# 300A_Hall_Power_Meter.net
KiCad netlist of a schematic drawn in EasyEDA Pro
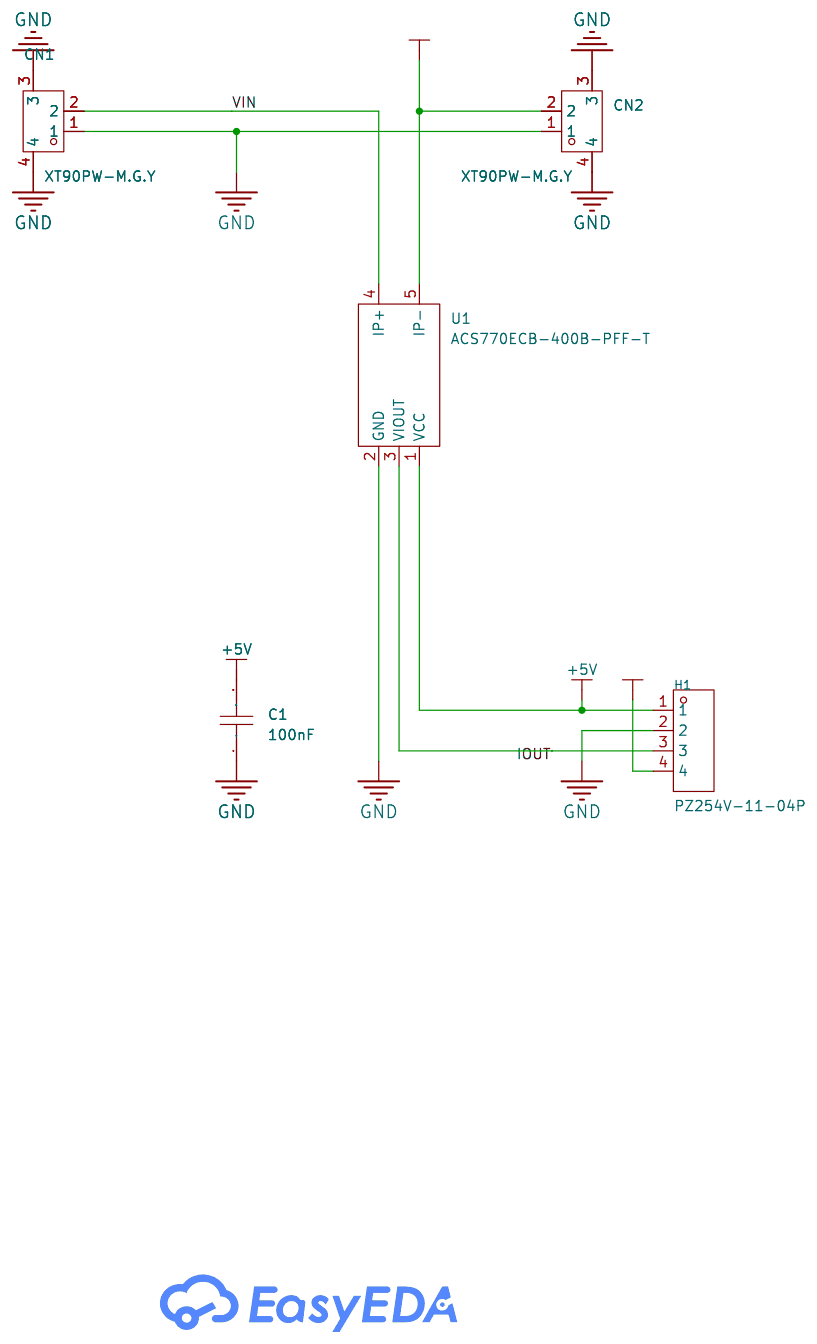
[diagram p0: Current Meter]
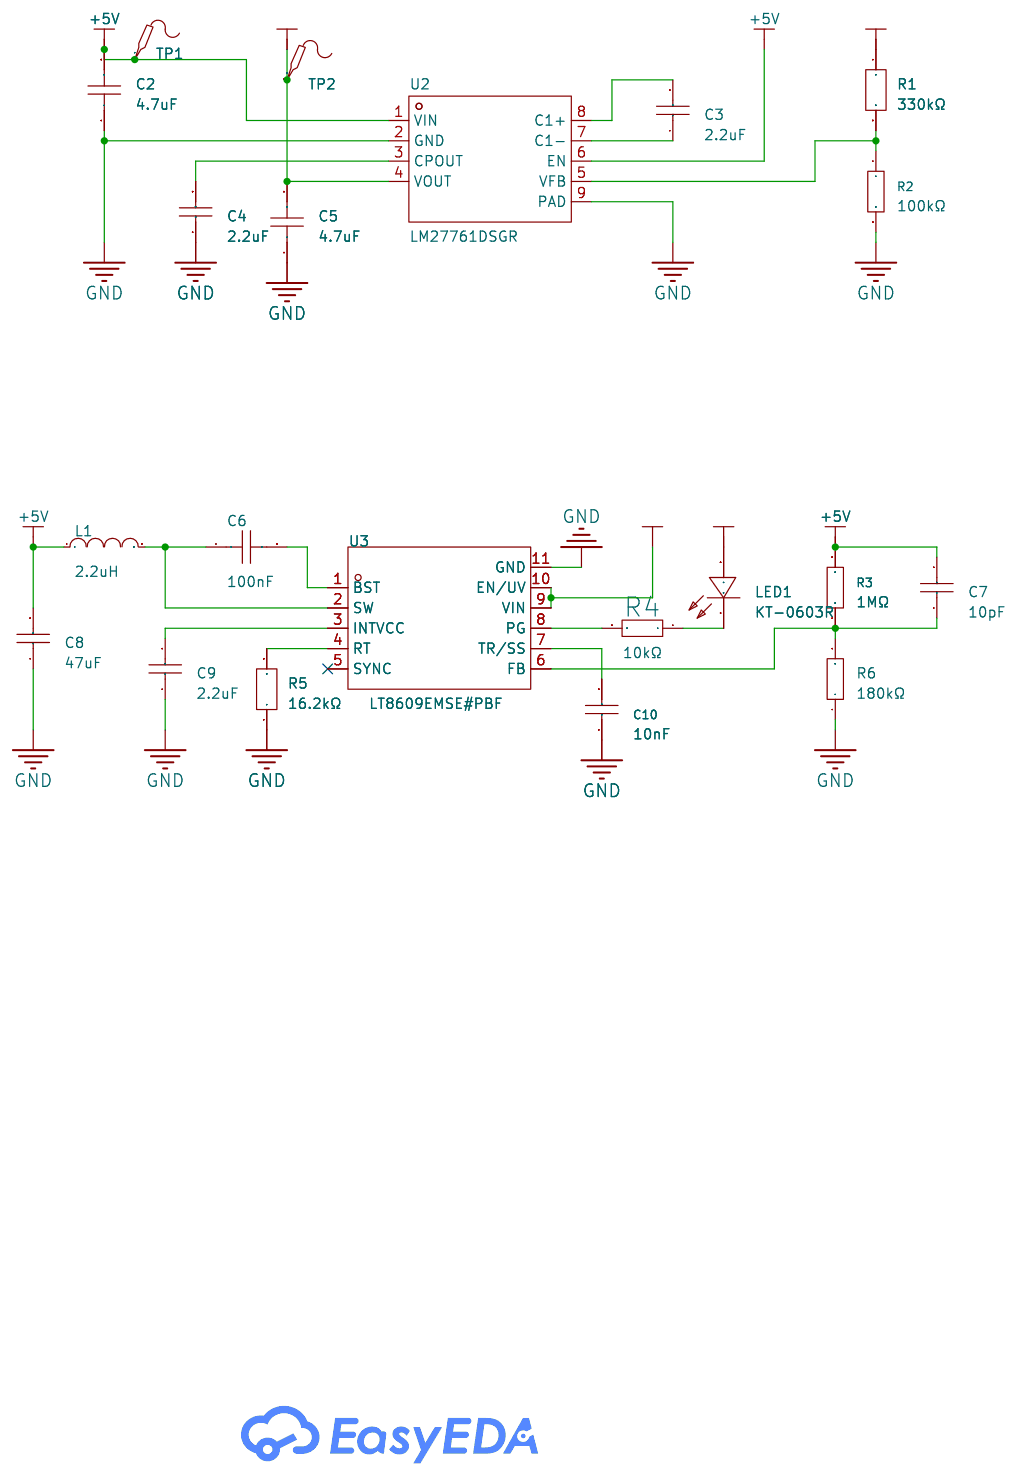
[diagram p1: Buck Converter]
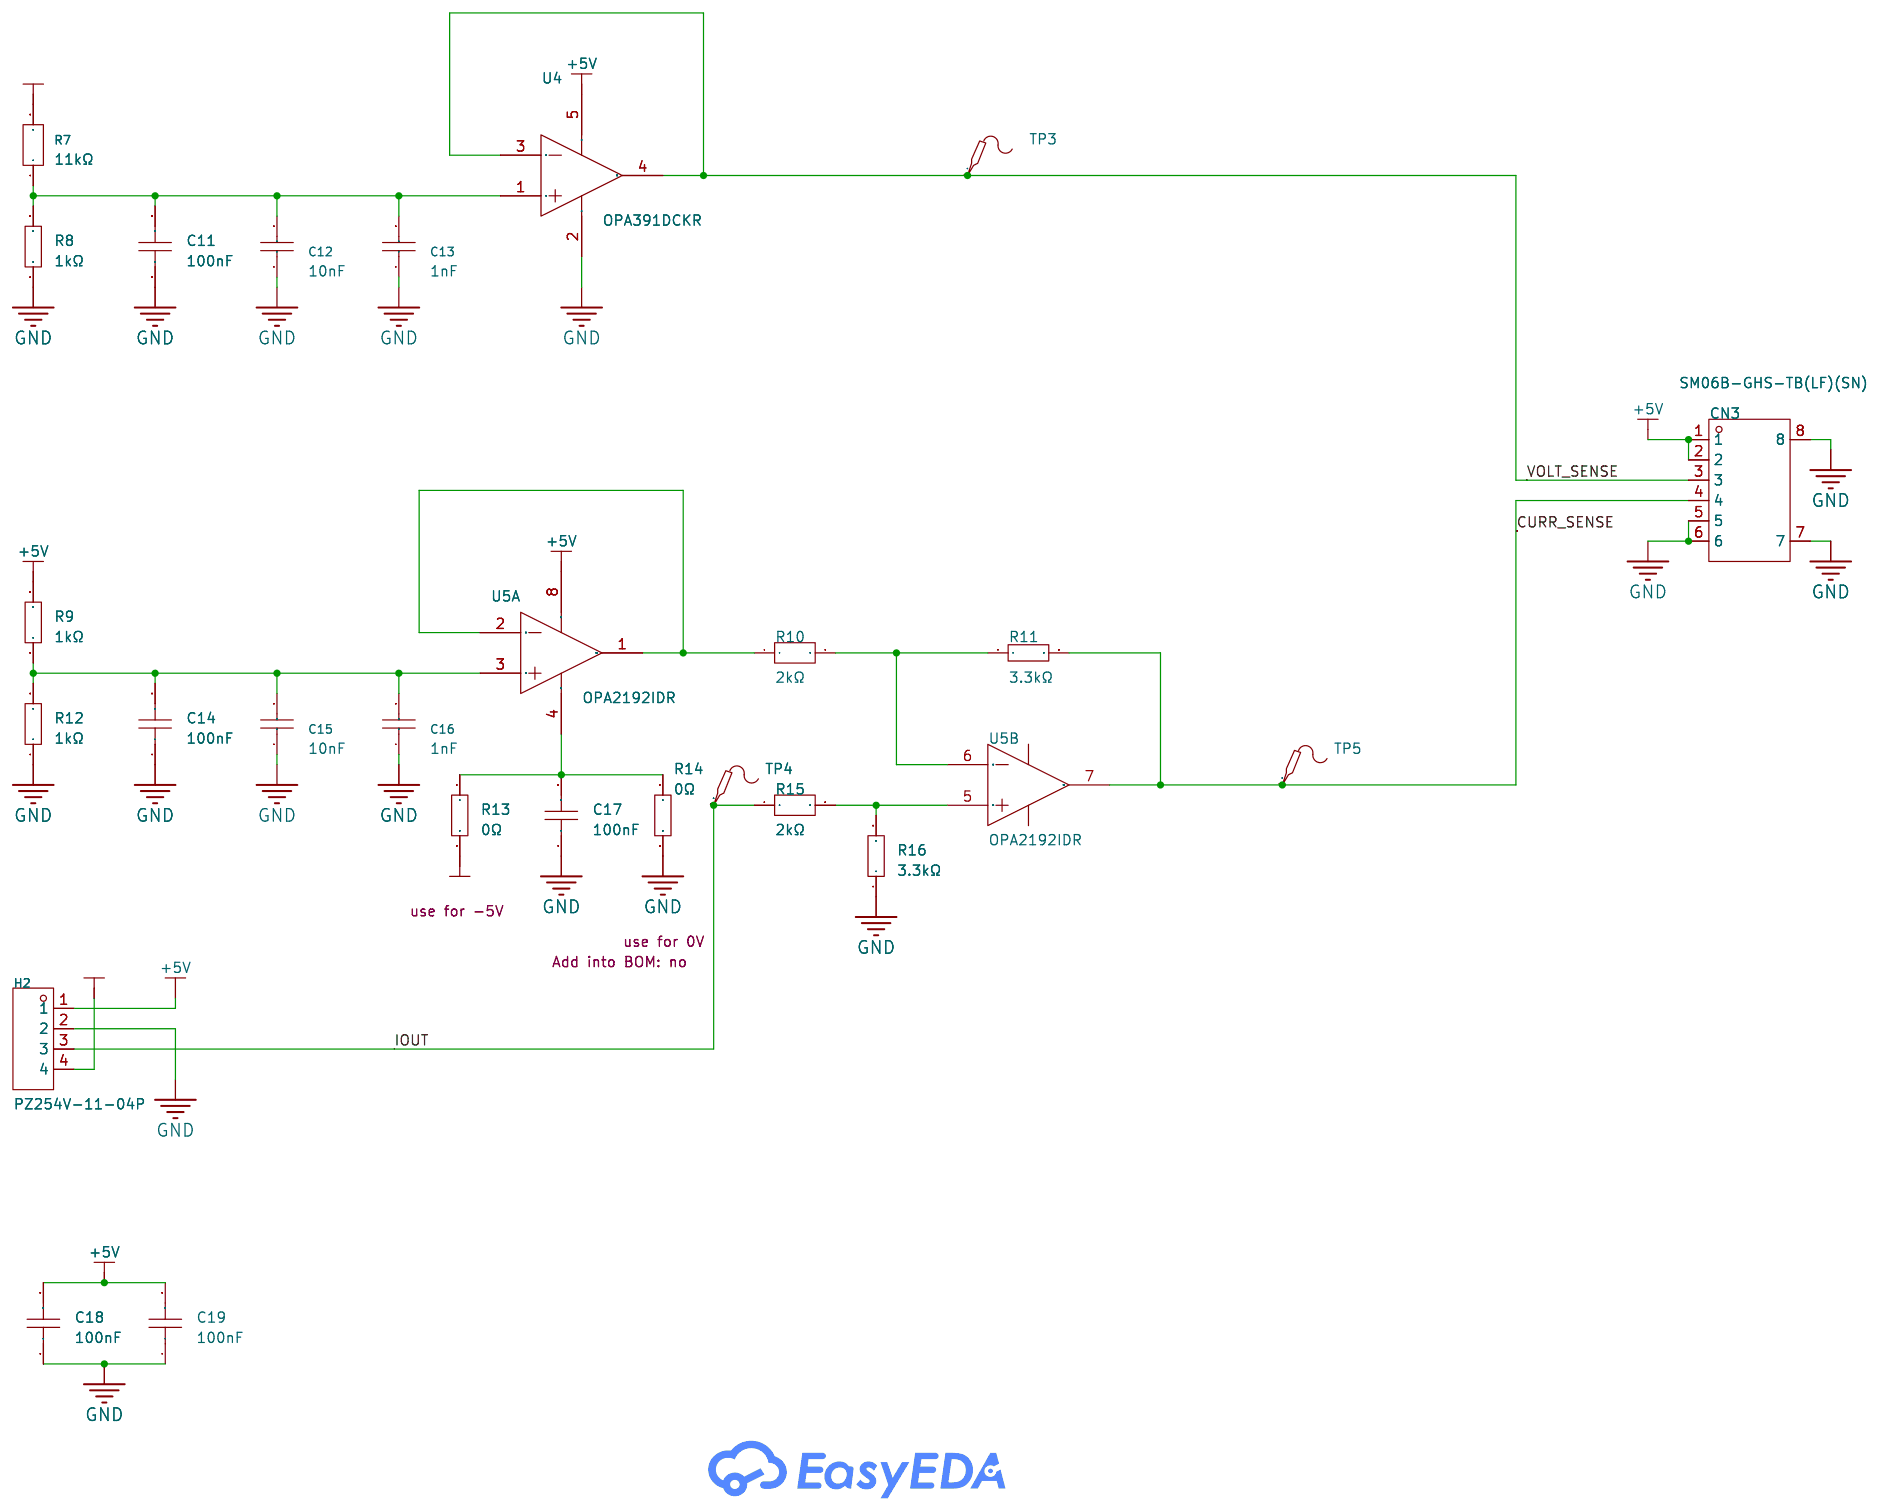
[diagram p2: Signal Processing]

(export (version "E")
  (design (tool "Eeschema 10.0.6"))
  (components
    (comp (ref "C1")
      (value "100nF")
      (footprint "easyedapro:C0402")
      (description "Capacitance:100nF Tolerance:±10% Tolerance:±10% Voltage Rating:16V Temperature Coefficient:X7R")
      (fields
        (field (name "Manufacturer Part") "CL05B104KO5NNNC")
        (field (name "Manufacturer") "SAMSUNG(三星)")
      )
      (libsource (lib "easyedapro") (part "CL05B104KO5NNNC"))
    )
    (comp (ref "CN1")
      (value "XT90PW-M.G.Y")
      (footprint "easyedapro:CONN-TH_XT90PW-M.G.Y")
      (fields (field (name "Manufacturer") "AMASS(艾迈斯)"))
      (libsource (lib "easyedapro") (part "XT90PW-M.G.Y"))
    )
    (comp (ref "CN2")
      (value "XT90PW-M.G.Y")
      (footprint "easyedapro:CONN-TH_XT90PW-M.G.Y")
      (fields (field (name "Manufacturer") "AMASS(艾迈斯)"))
      (libsource (lib "easyedapro") (part "XT90PW-M.G.Y"))
    )
    (comp (ref "H1")
      (value "PZ254V-11-04P")
      (footprint "easyedapro:HDR-TH_4P-P2.54-V-M")
      (fields (field (name "Manufacturer") "XFCN(兴飞)"))
      (libsource (lib "easyedapro") (part "PZ254V-11-04P_C2691448"))
    )
    (comp (ref "U1")
      (value "ACS770ECB-400B-PFF-T")
      (footprint "easyedapro:CB-5_L13.0-W10.0-P1.91-LS21.4-BR")
      (fields (field (name "Manufacturer") "ALLEGRO(美国埃戈罗)"))
      (libsource (lib "easyedapro") (part "ACS770ECB-400B-PFF-T"))
    )
    (comp (ref "C2")
      (value "4.7uF")
      (footprint "easyedapro:C0603")
      (description "Capacitance:4.7uF Tolerance:±10% Tolerance:±10% Voltage Rating:16V Temperature Coefficient:X5R")
      (fields
        (field (name "Manufacturer Part") "CL10A475KO8NNNC")
        (field (name "Manufacturer") "SAMSUNG(三星)")
      )
      (libsource (lib "easyedapro") (part "CL10A475KO8NNNC"))
    )
    (comp (ref "C3")
      (value "2.2uF")
      (footprint "easyedapro:C0603")
      (description "Capacitance:2.2uF Tolerance:±10% Tolerance:±10% Voltage Rating:16V Temperature Coefficient:X5R")
      (fields
        (field (name "Manufacturer Part") "CL10A225KO8NNNC")
        (field (name "Manufacturer") "SAMSUNG(三星)")
      )
      (libsource (lib "easyedapro") (part "CL10A225KO8NNNC"))
    )
    (comp (ref "C4")
      (value "2.2uF")
      (footprint "easyedapro:C0603")
      (description "Capacitance:2.2uF Tolerance:±10% Tolerance:±10% Voltage Rating:16V Temperature Coefficient:X5R")
      (fields
        (field (name "Manufacturer Part") "CL10A225KO8NNNC")
        (field (name "Manufacturer") "SAMSUNG(三星)")
      )
      (libsource (lib "easyedapro") (part "CL10A225KO8NNNC"))
    )
    (comp (ref "C5")
      (value "4.7uF")
      (footprint "easyedapro:C0603")
      (description "Capacitance:4.7uF Tolerance:±10% Tolerance:±10% Voltage Rating:16V Temperature Coefficient:X5R")
      (fields
        (field (name "Manufacturer Part") "CL10A475KO8NNNC")
        (field (name "Manufacturer") "SAMSUNG(三星)")
      )
      (libsource (lib "easyedapro") (part "CL10A475KO8NNNC"))
    )
    (comp (ref "C6")
      (value "100nF")
      (footprint "easyedapro:C0603")
      (description "Capacitance:100nF Tolerance:±10% Tolerance:±10% Voltage Rating:50V Temperature Coefficient:X7R")
      (fields
        (field (name "Manufacturer Part") "CC0603KRX7R9BB104")
        (field (name "Manufacturer") "YAGEO(国巨)")
      )
      (libsource (lib "easyedapro") (part "CC0603KRX7R9BB104"))
    )
    (comp (ref "C7")
      (value "10pF")
      (footprint "easyedapro:C0603")
      (description "Capacitance:10pF Tolerance:±5% Tolerance:±5% Voltage Rating:50V Temperature Coefficient:C0G")
      (fields
        (field (name "Manufacturer Part") "CL10C100JB8NNNC")
        (field (name "Manufacturer") "SAMSUNG(三星)")
      )
      (libsource (lib "easyedapro") (part "CL10C100JB8NNNC"))
    )
    (comp (ref "C8")
      (value "47uF")
      (footprint "easyedapro:C0805")
      (description "Capacitance:47uF Tolerance:±20% Tolerance:±20% Voltage Rating:6.3V Temperature Coefficient:X5R")
      (fields
        (field (name "Manufacturer Part") "CL21A476MQYNNNE")
        (field (name "Manufacturer") "SAMSUNG(三星)")
      )
      (libsource (lib "easyedapro") (part "CL21A476MQYNNNE"))
    )
    (comp (ref "C9")
      (value "2.2uF")
      (footprint "easyedapro:C0603")
      (description "Capacitance:2.2uF Tolerance:±10% Tolerance:±10% Voltage Rating:16V Temperature Coefficient:X5R")
      (fields
        (field (name "Manufacturer Part") "CL10A225KO8NNNC")
        (field (name "Manufacturer") "SAMSUNG(三星)")
      )
      (libsource (lib "easyedapro") (part "CL10A225KO8NNNC"))
    )
    (comp (ref "C10")
      (value "10nF")
      (footprint "easyedapro:C0603")
      (description "Capacitance:10nF Tolerance:±10% Tolerance:±10% Voltage Rating:50V Temperature Coefficient:X7R")
      (fields (field (name "Manufacturer Part") "0603B103K500NT") (field (name "Manufacturer") "FH(风华)"))
      (libsource (lib "easyedapro") (part "0603B103K500NT"))
    )
    (comp (ref "L1")
      (value "2.2uH")
      (footprint "easyedapro:IND-SMD_L4.4-W4.0_PHC0420")
      (fields (field (name "Manufacturer Part") "APH0420T2R2M") (field (name "Manufacturer") "APV(爱普微)"))
      (libsource (lib "easyedapro") (part "APH0420T2R2M"))
    )
    (comp (ref "LED1")
      (value "KT-0603R")
      (footprint "easyedapro:LED0603-RD")
      (fields (field (name "Manufacturer") "KENTO"))
      (libsource (lib "easyedapro") (part "KT-0603R"))
    )
    (comp (ref "R1")
      (value "330kΩ")
      (footprint "easyedapro:R0603")
      (fields (field (name "Manufacturer Part") "FRC0603F3303TS") (field (name "Manufacturer") "FOJAN(富捷)"))
      (libsource (lib "easyedapro") (part "FRC0603F3303TS"))
    )
    (comp (ref "R2")
      (value "100kΩ")
      (footprint "easyedapro:R0603")
      (fields (field (name "Manufacturer Part") "RC0603FR-07100KL") (field (name "Manufacturer") "YAGEO(国巨)"))
      (libsource (lib "easyedapro") (part "RC0603FR-07100KL"))
    )
    (comp (ref "R3")
      (value "1MΩ")
      (footprint "easyedapro:R0603")
      (fields
        (field (name "Manufacturer Part") "0603WAF1004T5E")
        (field (name "Manufacturer") "UNI-ROYAL(厚声)")
      )
      (libsource (lib "easyedapro") (part "0603WAF1004T5E"))
    )
    (comp (ref "R4")
      (value "10kΩ")
      (footprint "easyedapro:R0603")
      (fields
        (field (name "Manufacturer Part") "0603WAF1002T5E")
        (field (name "Manufacturer") "UNI-ROYAL(厚声)")
      )
      (libsource (lib "easyedapro") (part "0603WAF1002T5E"))
    )
    (comp (ref "R5")
      (value "16.2kΩ")
      (footprint "easyedapro:R0603")
      (fields (field (name "Manufacturer Part") "RT0603BRD0716K2L") (field (name "Manufacturer") "YAGEO(国巨)"))
      (libsource (lib "easyedapro") (part "RT0603BRD0716K2L"))
    )
    (comp (ref "R6")
      (value "180kΩ")
      (footprint "easyedapro:R0603")
      (fields
        (field (name "Manufacturer Part") "0603WAF1803T5E")
        (field (name "Manufacturer") "UNI-ROYAL(厚声)")
      )
      (libsource (lib "easyedapro") (part "0603WAF1803T5E"))
    )
    (comp (ref "TP1")
      (value "~")
      (footprint "easyedapro:Test-Point-0.5mm")
      (description "Test Point 测试点")
      (libsource (lib "easyedapro") (part "Test-Point"))
    )
    (comp (ref "TP2")
      (value "~")
      (footprint "easyedapro:Test-Point-0.5mm")
      (description "Test Point 测试点")
      (libsource (lib "easyedapro") (part "Test-Point"))
    )
    (comp (ref "U2")
      (value "LM27761DSGR")
      (footprint "easyedapro:WSON-8_L2.0-W2.0-P0.65-BL-EP")
      (fields (field (name "Manufacturer") "TI(德州仪器)"))
      (libsource (lib "easyedapro") (part "LM27761DSGR"))
    )
    (comp (ref "U3")
      (value "LT8609EMSE#PBF")
      (footprint "easyedapro:MSOP-10_L3.0-W3.0-P0.50-LS5.0-BL-EP")
      (fields (field (name "Manufacturer") "ADI(亚德诺)"))
      (libsource (lib "easyedapro") (part "LT8609EMSE#PBF"))
    )
    (comp (ref "C11")
      (value "100nF")
      (footprint "easyedapro:C0402")
      (description "Capacitance:100nF Tolerance:±10% Tolerance:±10% Voltage Rating:16V Temperature Coefficient:X7R")
      (fields
        (field (name "Manufacturer Part") "CL05B104KO5NNNC")
        (field (name "Manufacturer") "SAMSUNG(三星)")
      )
      (libsource (lib "easyedapro") (part "CL05B104KO5NNNC"))
    )
    (comp (ref "C12")
      (value "10nF")
      (footprint "easyedapro:C0603")
      (description "Capacitance:10nF Tolerance:±10% Tolerance:±10% Voltage Rating:50V Temperature Coefficient:X7R")
      (fields (field (name "Manufacturer Part") "0603B103K500NT") (field (name "Manufacturer") "FH(风华)"))
      (libsource (lib "easyedapro") (part "0603B103K500NT"))
    )
    (comp (ref "C13")
      (value "1nF")
      (footprint "easyedapro:C0603")
      (description "Capacitance:1nF Tolerance:±10% Tolerance:±10% Voltage Rating:50V Temperature Coefficient:X7R")
      (fields
        (field (name "Manufacturer Part") "CL10B102KB8NNNC")
        (field (name "Manufacturer") "SAMSUNG(三星)")
      )
      (libsource (lib "easyedapro") (part "CL10B102KB8NNNC"))
    )
    (comp (ref "C14")
      (value "100nF")
      (footprint "easyedapro:C0402")
      (description "Capacitance:100nF Tolerance:±10% Tolerance:±10% Voltage Rating:16V Temperature Coefficient:X7R")
      (fields
        (field (name "Manufacturer Part") "CL05B104KO5NNNC")
        (field (name "Manufacturer") "SAMSUNG(三星)")
      )
      (libsource (lib "easyedapro") (part "CL05B104KO5NNNC"))
    )
    (comp (ref "C15")
      (value "10nF")
      (footprint "easyedapro:C0603")
      (description "Capacitance:10nF Tolerance:±10% Tolerance:±10% Voltage Rating:50V Temperature Coefficient:X7R")
      (fields (field (name "Manufacturer Part") "0603B103K500NT") (field (name "Manufacturer") "FH(风华)"))
      (libsource (lib "easyedapro") (part "0603B103K500NT"))
    )
    (comp (ref "C16")
      (value "1nF")
      (footprint "easyedapro:C0603")
      (description "Capacitance:1nF Tolerance:±10% Tolerance:±10% Voltage Rating:50V Temperature Coefficient:X7R")
      (fields
        (field (name "Manufacturer Part") "CL10B102KB8NNNC")
        (field (name "Manufacturer") "SAMSUNG(三星)")
      )
      (libsource (lib "easyedapro") (part "CL10B102KB8NNNC"))
    )
    (comp (ref "C17")
      (value "100nF")
      (footprint "easyedapro:C0402")
      (description "Capacitance:100nF Tolerance:±10% Tolerance:±10% Voltage Rating:16V Temperature Coefficient:X7R")
      (fields
        (field (name "Manufacturer Part") "CL05B104KO5NNNC")
        (field (name "Manufacturer") "SAMSUNG(三星)")
      )
      (libsource (lib "easyedapro") (part "CL05B104KO5NNNC"))
    )
    (comp (ref "C18")
      (value "100nF")
      (footprint "easyedapro:C0402")
      (description "Capacitance:100nF Tolerance:±10% Tolerance:±10% Voltage Rating:16V Temperature Coefficient:X7R")
      (fields
        (field (name "Manufacturer Part") "CL05B104KO5NNNC")
        (field (name "Manufacturer") "SAMSUNG(三星)")
      )
      (libsource (lib "easyedapro") (part "CL05B104KO5NNNC"))
    )
    (comp (ref "C19")
      (value "100nF")
      (footprint "easyedapro:C0402")
      (description "Capacitance:100nF Tolerance:±10% Tolerance:±10% Voltage Rating:16V Temperature Coefficient:X7R")
      (fields
        (field (name "Manufacturer Part") "CL05B104KO5NNNC")
        (field (name "Manufacturer") "SAMSUNG(三星)")
      )
      (libsource (lib "easyedapro") (part "CL05B104KO5NNNC"))
    )
    (comp (ref "CN3")
      (value "SM06B-GHS-TB(LF)(SN)")
      (footprint "easyedapro:CONN-TH_SM06B-GHS-TB-LF-SN")
      (fields (field (name "Manufacturer") "JST"))
      (libsource (lib "easyedapro") (part "SM06B-GHS-TB(LF)(SN)"))
    )
    (comp (ref "H2")
      (value "PZ254V-11-04P")
      (footprint "easyedapro:HDR-TH_4P-P2.54-V-M")
      (fields (field (name "Manufacturer") "XFCN(兴飞)"))
      (libsource (lib "easyedapro") (part "PZ254V-11-04P_C2691448"))
    )
    (comp (ref "R7")
      (value "11kΩ")
      (footprint "easyedapro:R0603")
      (fields (field (name "Manufacturer Part") "ERA3AEB113V") (field (name "Manufacturer") "PANASONIC(松下)"))
      (libsource (lib "easyedapro") (part "ERA3AEB113V"))
    )
    (comp (ref "R8")
      (value "1kΩ")
      (footprint "easyedapro:R0603")
      (fields (field (name "Manufacturer Part") "RT0603BRD071KL") (field (name "Manufacturer") "YAGEO(国巨)"))
      (libsource (lib "easyedapro") (part "RT0603BRD071KL"))
    )
    (comp (ref "R9")
      (value "1kΩ")
      (footprint "easyedapro:R0603")
      (fields (field (name "Manufacturer Part") "RT0603BRD071KL") (field (name "Manufacturer") "YAGEO(国巨)"))
      (libsource (lib "easyedapro") (part "RT0603BRD071KL"))
    )
    (comp (ref "R10")
      (value "2kΩ")
      (footprint "easyedapro:R0603")
      (fields (field (name "Manufacturer Part") "RT0603BRD072KL") (field (name "Manufacturer") "YAGEO(国巨)"))
      (libsource (lib "easyedapro") (part "RT0603BRD072KL"))
    )
    (comp (ref "R11")
      (value "3.3kΩ")
      (footprint "easyedapro:R0603")
      (fields (field (name "Manufacturer Part") "RT0603BRD073K3L") (field (name "Manufacturer") "YAGEO(国巨)"))
      (libsource (lib "easyedapro") (part "RT0603BRD073K3L"))
    )
    (comp (ref "R12")
      (value "1kΩ")
      (footprint "easyedapro:R0603")
      (fields (field (name "Manufacturer Part") "RT0603BRD071KL") (field (name "Manufacturer") "YAGEO(国巨)"))
      (libsource (lib "easyedapro") (part "RT0603BRD071KL"))
    )
    (comp (ref "R13")
      (value "0Ω")
      (footprint "easyedapro:R0603")
      (fields
        (field (name "Manufacturer Part") "RC0603JR-070RL")
        (field (name "Manufacturer") "YAGEO(国巨)")
        (field (name "Comment") "use for -5V")
      )
      (libsource (lib "easyedapro") (part "RC0603JR-070RL"))
    )
    (comp (ref "R14")
      (value "0Ω")
      (footprint "easyedapro:R0603")
      (fields
        (field (name "Manufacturer Part") "RC0603JR-070RL")
        (field (name "Manufacturer") "YAGEO(国巨)")
        (field (name "Add into BOM") "no")
        (field (name "Comment") "use for 0V")
      )
      (libsource (lib "easyedapro") (part "RC0603JR-070RL"))
    )
    (comp (ref "R15")
      (value "2kΩ")
      (footprint "easyedapro:R0603")
      (fields (field (name "Manufacturer Part") "RT0603BRD072KL") (field (name "Manufacturer") "YAGEO(国巨)"))
      (libsource (lib "easyedapro") (part "RT0603BRD072KL"))
    )
    (comp (ref "R16")
      (value "3.3kΩ")
      (footprint "easyedapro:R0603")
      (fields (field (name "Manufacturer Part") "RT0603BRD073K3L") (field (name "Manufacturer") "YAGEO(国巨)"))
      (libsource (lib "easyedapro") (part "RT0603BRD073K3L"))
    )
    (comp (ref "TP3")
      (value "~")
      (footprint "easyedapro:Test-Point-0.5mm")
      (description "Test Point 测试点")
      (libsource (lib "easyedapro") (part "Test-Point"))
    )
    (comp (ref "TP4")
      (value "~")
      (footprint "easyedapro:Test-Point-0.5mm")
      (description "Test Point 测试点")
      (libsource (lib "easyedapro") (part "Test-Point"))
    )
    (comp (ref "TP5")
      (value "~")
      (footprint "easyedapro:Test-Point-0.5mm")
      (description "Test Point 测试点")
      (libsource (lib "easyedapro") (part "Test-Point"))
    )
    (comp (ref "U4")
      (value "OPA391DCKR")
      (footprint "easyedapro:SC-70-5_L2.1-W1.3-P0.65-LS2.1-BR")
      (fields (field (name "Manufacturer") "TI(德州仪器)"))
      (libsource (lib "easyedapro") (part "OPA391DCKR"))
    )
    (comp (ref "U5")
      (value "OPA2192IDR")
      (footprint "easyedapro:SOIC-8_L4.9-W3.9-P1.27-LS6.0-BL")
      (fields (field (name "Manufacturer") "TI(德州仪器)"))
      (libsource (lib "easyedapro") (part "OPA2192IDR"))
    )
  )
  (nets
    (net (code "1") (name "+5V") (class "Default")
      (node (ref "C1") (pin "2") (pinfunction "2_2") (pintype "unspecified"))
      (node (ref "C18") (pin "2") (pinfunction "2_2") (pintype "unspecified"))
      (node (ref "C19") (pin "2") (pinfunction "2_2") (pintype "unspecified"))
      (node (ref "C2") (pin "2") (pinfunction "2_2") (pintype "unspecified"))
      (node (ref "C7") (pin "2") (pinfunction "2_2") (pintype "input"))
      (node (ref "C8") (pin "2") (pinfunction "2_2") (pintype "input"))
      (node (ref "CN3") (pin "1") (pinfunction "1_1") (pintype "unspecified"))
      (node (ref "CN3") (pin "2") (pinfunction "2_2") (pintype "unspecified"))
      (node (ref "H1") (pin "1") (pinfunction "1_1") (pintype "input"))
      (node (ref "H2") (pin "1") (pinfunction "1_1") (pintype "input"))
      (node (ref "L1") (pin "1") (pinfunction "1_1") (pintype "unspecified"))
      (node (ref "R3") (pin "2") (pinfunction "2_2") (pintype "input"))
      (node (ref "R9") (pin "2") (pinfunction "2_2") (pintype "input"))
      (node (ref "TP1") (pin "1") (pinfunction "1_1") (pintype "unspecified"))
      (node (ref "U1") (pin "1") (pinfunction "VCC_1") (pintype "unspecified"))
      (node (ref "U2") (pin "1") (pinfunction "VIN_1") (pintype "unspecified"))
      (node (ref "U2") (pin "6") (pinfunction "EN_6") (pintype "unspecified"))
      (node (ref "U4") (pin "5") (pinfunction "V+_5") (pintype "unspecified"))
      (node (ref "U5") (pin "8") (pinfunction "VDD_8") (pintype "unspecified"))
    )
    (net (code "2") (name "-5V") (class "Default")
      (node (ref "C5") (pin "2") (pinfunction "2_2") (pintype "unspecified"))
      (node (ref "R1") (pin "1") (pinfunction "1_1") (pintype "unspecified"))
      (node (ref "R13") (pin "2") (pinfunction "2_2") (pintype "input"))
      (node (ref "TP2") (pin "1") (pinfunction "1_1") (pintype "unspecified"))
      (node (ref "U2") (pin "4") (pinfunction "VOUT_4") (pintype "unspecified"))
    )
    (net (code "3") (name "CURR_SENSE") (class "Default")
      (node (ref "CN3") (pin "4") (pinfunction "4_4") (pintype "unspecified"))
      (node (ref "R11") (pin "2") (pinfunction "2_2") (pintype "unspecified"))
      (node (ref "TP5") (pin "1") (pinfunction "1_1") (pintype "unspecified"))
      (node (ref "U5") (pin "7") (pinfunction "VOUTB_7") (pintype "output"))
    )
    (net (code "4") (name "GND") (class "Default")
      (node (ref "C1") (pin "1") (pinfunction "1_1") (pintype "unspecified"))
      (node (ref "C10") (pin "1") (pinfunction "1_1") (pintype "input"))
      (node (ref "C11") (pin "1") (pinfunction "1_1") (pintype "unspecified"))
      (node (ref "C12") (pin "1") (pinfunction "1_1") (pintype "input"))
      (node (ref "C13") (pin "1") (pinfunction "1_1") (pintype "input"))
      (node (ref "C14") (pin "1") (pinfunction "1_1") (pintype "unspecified"))
      (node (ref "C15") (pin "1") (pinfunction "1_1") (pintype "input"))
      (node (ref "C16") (pin "1") (pinfunction "1_1") (pintype "input"))
      (node (ref "C17") (pin "1") (pinfunction "1_1") (pintype "unspecified"))
      (node (ref "C18") (pin "1") (pinfunction "1_1") (pintype "unspecified"))
      (node (ref "C19") (pin "1") (pinfunction "1_1") (pintype "unspecified"))
      (node (ref "C2") (pin "1") (pinfunction "1_1") (pintype "unspecified"))
      (node (ref "C4") (pin "1") (pinfunction "1_1") (pintype "input"))
      (node (ref "C5") (pin "1") (pinfunction "1_1") (pintype "unspecified"))
      (node (ref "C8") (pin "1") (pinfunction "1_1") (pintype "input"))
      (node (ref "C9") (pin "1") (pinfunction "1_1") (pintype "input"))
      (node (ref "CN1") (pin "1") (pinfunction "1_1") (pintype "unspecified"))
      (node (ref "CN1") (pin "3") (pinfunction "3_3") (pintype "unspecified"))
      (node (ref "CN1") (pin "4") (pinfunction "4_4") (pintype "unspecified"))
      (node (ref "CN2") (pin "1") (pinfunction "1_1") (pintype "unspecified"))
      (node (ref "CN2") (pin "3") (pinfunction "3_3") (pintype "unspecified"))
      (node (ref "CN2") (pin "4") (pinfunction "4_4") (pintype "unspecified"))
      (node (ref "CN3") (pin "5") (pinfunction "5_5") (pintype "unspecified"))
      (node (ref "CN3") (pin "6") (pinfunction "6_6") (pintype "unspecified"))
      (node (ref "CN3") (pin "7") (pinfunction "7_7") (pintype "unspecified"))
      (node (ref "CN3") (pin "8") (pinfunction "8_8") (pintype "unspecified"))
      (node (ref "H1") (pin "2") (pinfunction "2_2") (pintype "input"))
      (node (ref "H2") (pin "2") (pinfunction "2_2") (pintype "input"))
      (node (ref "R12") (pin "1") (pinfunction "1_1") (pintype "input"))
      (node (ref "R14") (pin "2") (pinfunction "2_2") (pintype "input"))
      (node (ref "R16") (pin "1") (pinfunction "1_1") (pintype "unspecified"))
      (node (ref "R2") (pin "2") (pinfunction "2_2") (pintype "input"))
      (node (ref "R5") (pin "1") (pinfunction "1_1") (pintype "unspecified"))
      (node (ref "R6") (pin "1") (pinfunction "1_1") (pintype "input"))
      (node (ref "R8") (pin "1") (pinfunction "1_1") (pintype "input"))
      (node (ref "U1") (pin "2") (pinfunction "GND_2") (pintype "unspecified"))
      (node (ref "U2") (pin "2") (pinfunction "GND_2") (pintype "unspecified"))
      (node (ref "U2") (pin "9") (pinfunction "PAD_9") (pintype "unspecified"))
      (node (ref "U3") (pin "11") (pinfunction "GND_11") (pintype "unspecified"))
      (node (ref "U4") (pin "2") (pinfunction "V-_2") (pintype "unspecified"))
    )
    (net (code "5") (name "IOUT") (class "Default")
      (node (ref "H1") (pin "3") (pinfunction "3_3") (pintype "input"))
      (node (ref "H2") (pin "3") (pinfunction "3_3") (pintype "input"))
      (node (ref "R15") (pin "1") (pinfunction "1_1") (pintype "unspecified"))
      (node (ref "TP4") (pin "1") (pinfunction "1_1") (pintype "unspecified"))
      (node (ref "U1") (pin "3") (pinfunction "VIOUT_3") (pintype "unspecified"))
    )
    (net (code "6") (name "Net-(LED1-K)") (class "Default")
      (node (ref "LED1") (pin "1") (pinfunction "K_1") (pintype "unspecified"))
      (node (ref "R4") (pin "1") (pinfunction "1_1") (pintype "input"))
    )
    (net (code "7") (name "Net-(U2-C1+)") (class "Default")
      (node (ref "C3") (pin "2") (pinfunction "2_2") (pintype "input"))
      (node (ref "U2") (pin "8") (pinfunction "C1+_8") (pintype "unspecified"))
    )
    (net (code "8") (name "Net-(U2-C1-)") (class "Default")
      (node (ref "C3") (pin "1") (pinfunction "1_1") (pintype "input"))
      (node (ref "U2") (pin "7") (pinfunction "C1-_7") (pintype "unspecified"))
    )
    (net (code "9") (name "Net-(U2-CPOUT)") (class "Default")
      (node (ref "C4") (pin "2") (pinfunction "2_2") (pintype "input"))
      (node (ref "U2") (pin "3") (pinfunction "CPOUT_3") (pintype "unspecified"))
    )
    (net (code "10") (name "Net-(U2-VFB)") (class "Default")
      (node (ref "R1") (pin "2") (pinfunction "2_2") (pintype "unspecified"))
      (node (ref "R2") (pin "1") (pinfunction "1_1") (pintype "input"))
      (node (ref "U2") (pin "5") (pinfunction "VFB_5") (pintype "unspecified"))
    )
    (net (code "11") (name "Net-(U3-BST)") (class "Default")
      (node (ref "C6") (pin "2") (pinfunction "2_2") (pintype "unspecified"))
      (node (ref "U3") (pin "1") (pinfunction "BST_1") (pintype "unspecified"))
    )
    (net (code "12") (name "Net-(U3-FB)") (class "Default")
      (node (ref "C7") (pin "1") (pinfunction "1_1") (pintype "input"))
      (node (ref "R3") (pin "1") (pinfunction "1_1") (pintype "input"))
      (node (ref "R6") (pin "2") (pinfunction "2_2") (pintype "input"))
      (node (ref "U3") (pin "6") (pinfunction "FB_6") (pintype "unspecified"))
    )
    (net (code "13") (name "Net-(U3-INTVCC)") (class "Default")
      (node (ref "C9") (pin "2") (pinfunction "2_2") (pintype "input"))
      (node (ref "U3") (pin "3") (pinfunction "INTVCC_3") (pintype "unspecified"))
    )
    (net (code "14") (name "Net-(U3-PG)") (class "Default")
      (node (ref "R4") (pin "2") (pinfunction "2_2") (pintype "input"))
      (node (ref "U3") (pin "8") (pinfunction "PG_8") (pintype "unspecified"))
    )
    (net (code "15") (name "Net-(U3-RT)") (class "Default")
      (node (ref "R5") (pin "2") (pinfunction "2_2") (pintype "unspecified"))
      (node (ref "U3") (pin "4") (pinfunction "RT_4") (pintype "unspecified"))
    )
    (net (code "16") (name "Net-(U3-SW)") (class "Default")
      (node (ref "C6") (pin "1") (pinfunction "1_1") (pintype "unspecified"))
      (node (ref "L1") (pin "2") (pinfunction "2_2") (pintype "unspecified"))
      (node (ref "U3") (pin "2") (pinfunction "SW_2") (pintype "unspecified"))
    )
    (net (code "17") (name "Net-(U3-TR{slash}SS)") (class "Default")
      (node (ref "C10") (pin "2") (pinfunction "2_2") (pintype "input"))
      (node (ref "U3") (pin "7") (pinfunction "TR/SS_7") (pintype "unspecified"))
    )
    (net (code "18") (name "Net-(U4-IN+)") (class "Default")
      (node (ref "C11") (pin "2") (pinfunction "2_2") (pintype "unspecified"))
      (node (ref "C12") (pin "2") (pinfunction "2_2") (pintype "input"))
      (node (ref "C13") (pin "2") (pinfunction "2_2") (pintype "input"))
      (node (ref "R7") (pin "1") (pinfunction "1_1") (pintype "input"))
      (node (ref "R8") (pin "2") (pinfunction "2_2") (pintype "input"))
      (node (ref "U4") (pin "1") (pinfunction "IN+_1") (pintype "unspecified"))
    )
    (net (code "19") (name "Net-(U5A-VINA+)") (class "Default")
      (node (ref "C14") (pin "2") (pinfunction "2_2") (pintype "unspecified"))
      (node (ref "C15") (pin "2") (pinfunction "2_2") (pintype "input"))
      (node (ref "C16") (pin "2") (pinfunction "2_2") (pintype "input"))
      (node (ref "R12") (pin "2") (pinfunction "2_2") (pintype "input"))
      (node (ref "R9") (pin "1") (pinfunction "1_1") (pintype "input"))
      (node (ref "U5") (pin "3") (pinfunction "VINA+_3") (pintype "unspecified"))
    )
    (net (code "20") (name "Net-(U5A-VINA-)") (class "Default")
      (node (ref "R10") (pin "1") (pinfunction "1_1") (pintype "unspecified"))
      (node (ref "U5") (pin "1") (pinfunction "VOUTA_1") (pintype "output"))
      (node (ref "U5") (pin "2") (pinfunction "VINA-_2") (pintype "unspecified"))
    )
    (net (code "21") (name "Net-(U5A-VSS)") (class "Default")
      (node (ref "C17") (pin "2") (pinfunction "2_2") (pintype "unspecified"))
      (node (ref "R13") (pin "1") (pinfunction "1_1") (pintype "input"))
      (node (ref "R14") (pin "1") (pinfunction "1_1") (pintype "input"))
      (node (ref "U5") (pin "4") (pinfunction "VSS_4") (pintype "unspecified"))
    )
    (net (code "22") (name "Net-(U5B-VINB+)") (class "Default")
      (node (ref "R15") (pin "2") (pinfunction "2_2") (pintype "unspecified"))
      (node (ref "R16") (pin "2") (pinfunction "2_2") (pintype "unspecified"))
      (node (ref "U5") (pin "5") (pinfunction "VINB+_5") (pintype "unspecified"))
    )
    (net (code "23") (name "Net-(U5B-VINB-)") (class "Default")
      (node (ref "R10") (pin "2") (pinfunction "2_2") (pintype "unspecified"))
      (node (ref "R11") (pin "1") (pinfunction "1_1") (pintype "unspecified"))
      (node (ref "U5") (pin "6") (pinfunction "VINB-_6") (pintype "unspecified"))
    )
    (net (code "24") (name "VIN") (class "Default")
      (node (ref "CN1") (pin "2") (pinfunction "2_2") (pintype "unspecified"))
      (node (ref "U1") (pin "4") (pinfunction "IP+_4") (pintype "unspecified"))
    )
    (net (code "25") (name "VOLT_SENSE") (class "Default")
      (node (ref "CN3") (pin "3") (pinfunction "3_3") (pintype "unspecified"))
      (node (ref "TP3") (pin "1") (pinfunction "1_1") (pintype "unspecified"))
      (node (ref "U4") (pin "3") (pinfunction "IN-_3") (pintype "unspecified"))
      (node (ref "U4") (pin "4") (pinfunction "OUT_4") (pintype "output"))
    )
    (net (code "26") (name "VOUT") (class "Default")
      (node (ref "CN2") (pin "2") (pinfunction "2_2") (pintype "unspecified"))
      (node (ref "H1") (pin "4") (pinfunction "4_4") (pintype "input"))
      (node (ref "H2") (pin "4") (pinfunction "4_4") (pintype "input"))
      (node (ref "LED1") (pin "2") (pinfunction "A_2") (pintype "unspecified"))
      (node (ref "R7") (pin "2") (pinfunction "2_2") (pintype "input"))
      (node (ref "U1") (pin "5") (pinfunction "IP-_5") (pintype "unspecified"))
      (node (ref "U3") (pin "10") (pinfunction "EN/UV_10") (pintype "unspecified"))
      (node (ref "U3") (pin "9") (pinfunction "VIN_9") (pintype "unspecified"))
    )
    (net (code "27") (name "unconnected-(U3-SYNC-Pad5)") (class "Default")
      (node (ref "U3") (pin "5") (pinfunction "SYNC_5") (pintype "unspecified+no_connect"))
    )
  )
)
